# L-D5019-01-05.net
KiCad netlist of a schematic drawn in Altium Designer
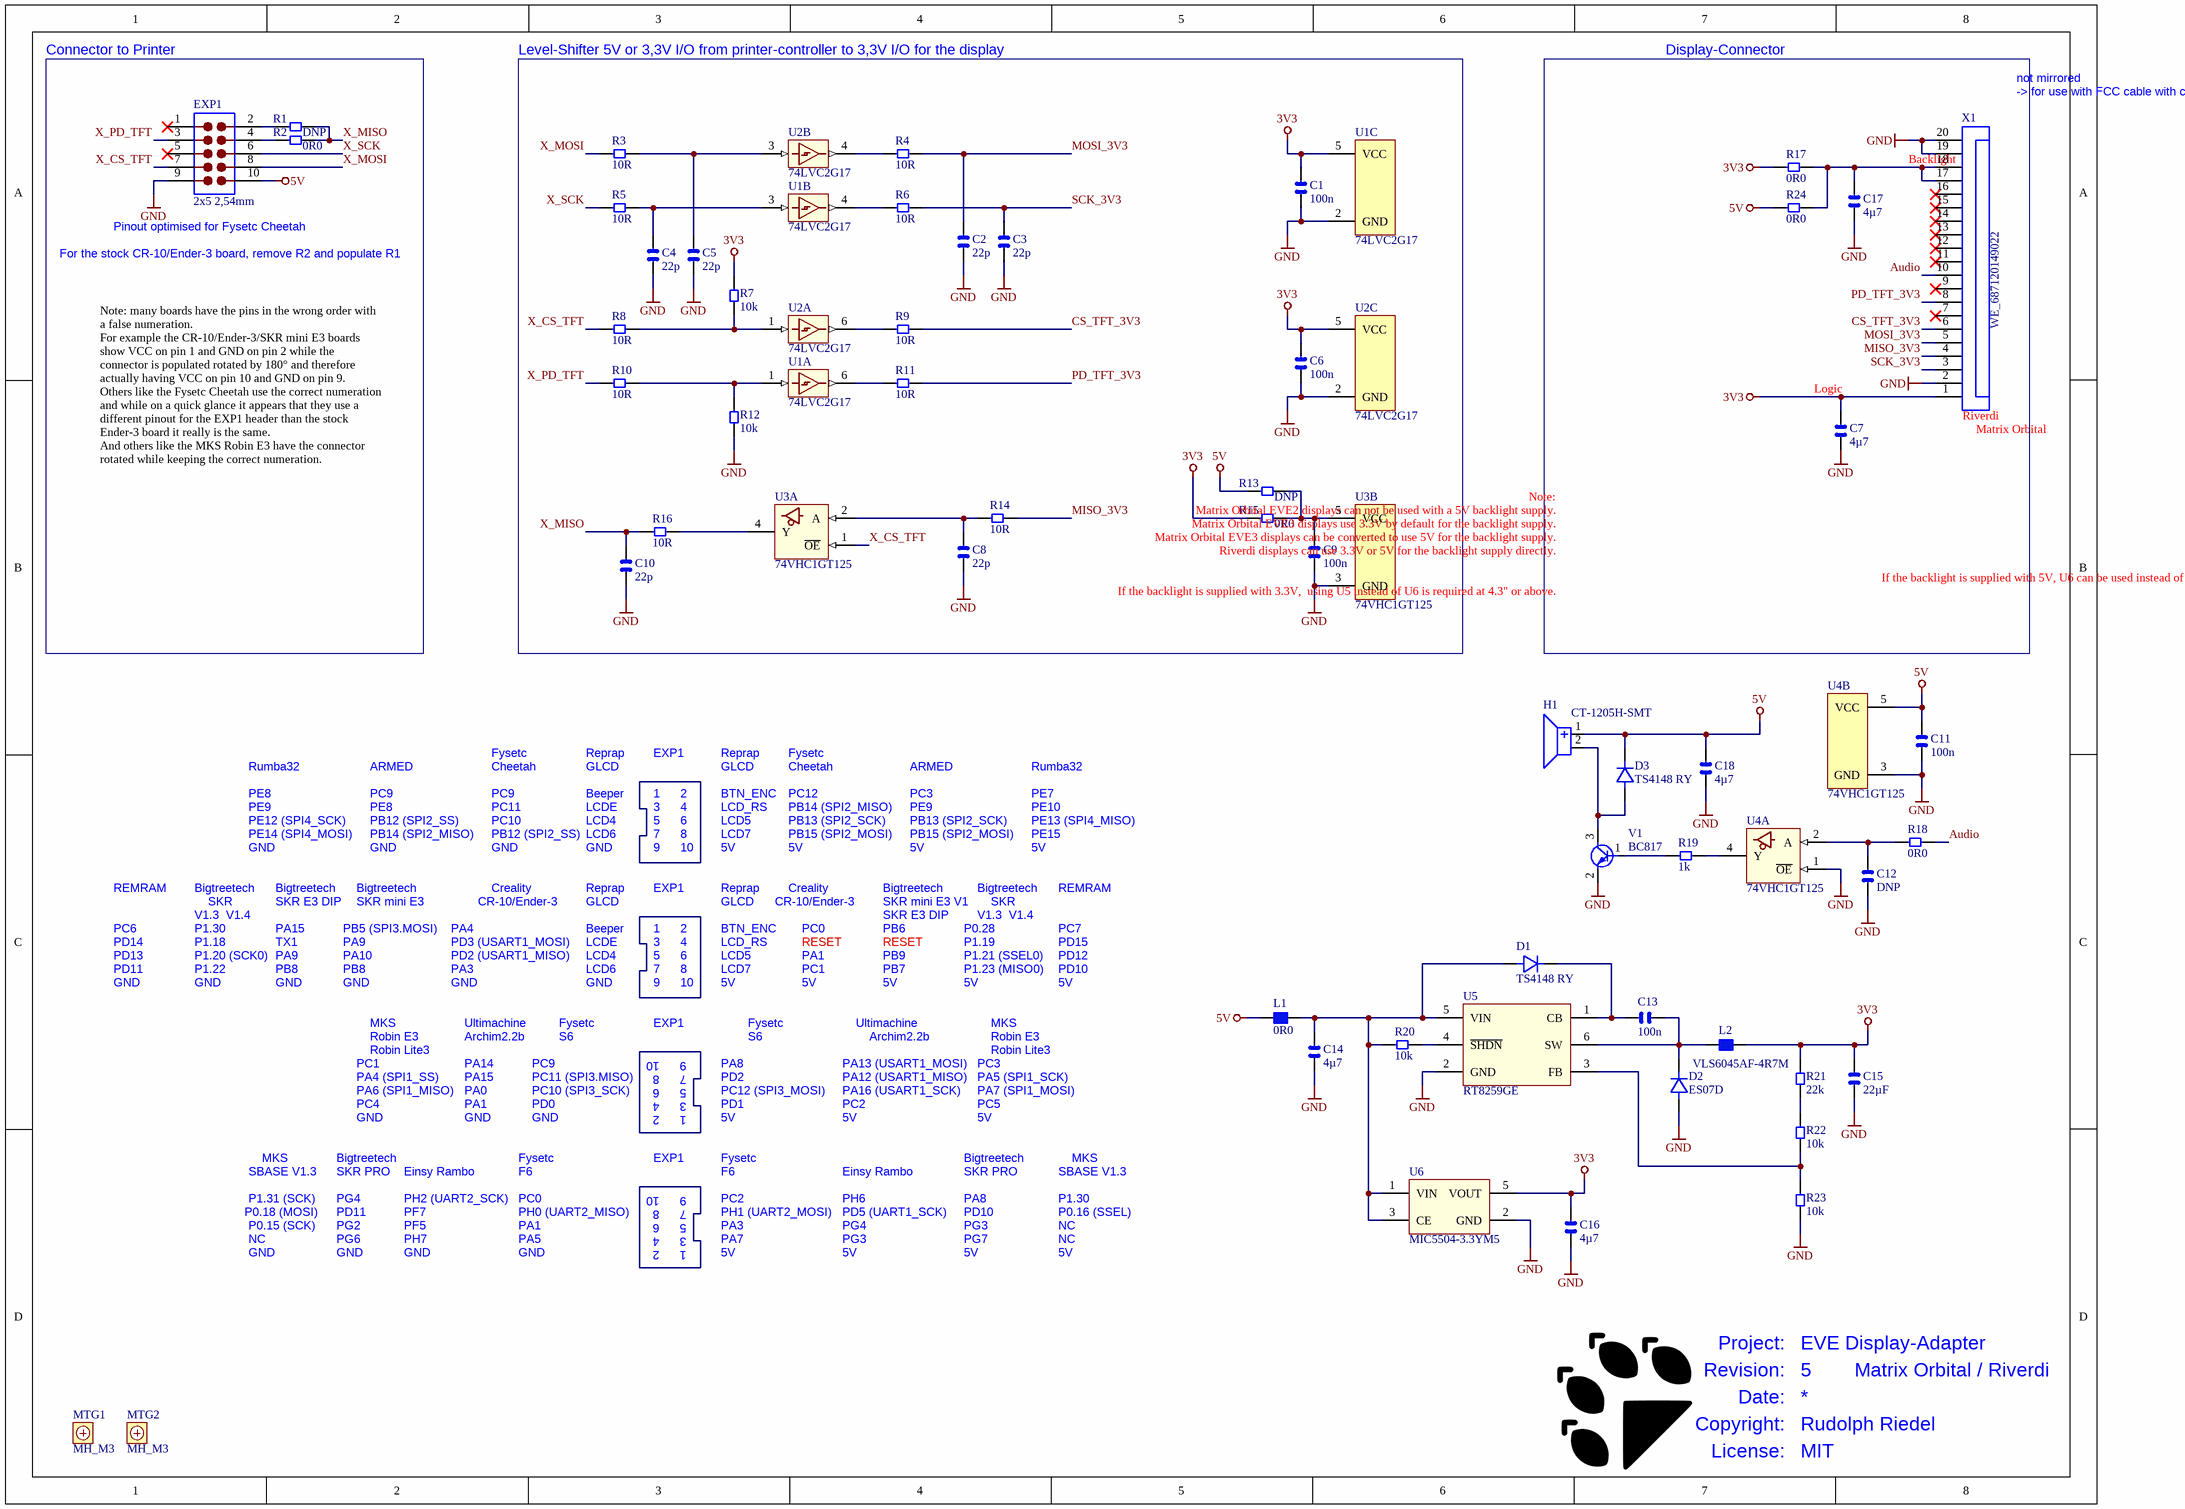
[diagram p0: L-D5019-01-05.SchDoc]

(export (version "E")
  (design (tool "Eeschema 10.0.6"))
  (components
    (comp (ref "C1")
      (value "100n")
      (footprint "CAPC2012X14L")
      (description "0805 Chip Capacitor")
      (fields (field (name "PART NUMBER") "CAPC_0805") (field (name "EDITOR") "rriedel"))
      (libsource (lib "HW-Labor_GF") (part "CAP_2_V2"))
    )
    (comp (ref "C2")
      (value "22p")
      (footprint "CAPC2012X14L")
      (description "0805 Chip Capacitor")
      (fields (field (name "PART NUMBER") "CAPC_0805") (field (name "EDITOR") "rriedel"))
      (libsource (lib "HW-Labor_GF") (part "CAP_2_V2"))
    )
    (comp (ref "C3")
      (value "22p")
      (footprint "CAPC2012X14L")
      (description "0805 Chip Capacitor")
      (fields (field (name "PART NUMBER") "CAPC_0805") (field (name "EDITOR") "rriedel"))
      (libsource (lib "HW-Labor_GF") (part "CAP_2_V2"))
    )
    (comp (ref "C4")
      (value "22p")
      (footprint "CAPC2012X14L")
      (description "0805 Chip Capacitor")
      (fields (field (name "PART NUMBER") "CAPC_0805") (field (name "EDITOR") "rriedel"))
      (libsource (lib "HW-Labor_GF") (part "CAP_2_V2"))
    )
    (comp (ref "C5")
      (value "22p")
      (footprint "CAPC2012X14L")
      (description "0805 Chip Capacitor")
      (fields (field (name "PART NUMBER") "CAPC_0805") (field (name "EDITOR") "rriedel"))
      (libsource (lib "HW-Labor_GF") (part "CAP_2_V2"))
    )
    (comp (ref "C6")
      (value "100n")
      (footprint "CAPC2012X14L")
      (description "0805 Chip Capacitor")
      (fields (field (name "PART NUMBER") "CAPC_0805") (field (name "EDITOR") "rriedel"))
      (libsource (lib "HW-Labor_GF") (part "CAP_2_V2"))
    )
    (comp (ref "C7")
      (value "4µ7")
      (footprint "CAPC2012X14L")
      (description "0805 Chip Capacitor")
      (fields (field (name "PART NUMBER") "CAPC_0805") (field (name "ERSTELLER") "rriedel"))
      (libsource (lib "HW-Labor_GF") (part "CAP_2_V2"))
    )
    (comp (ref "C8")
      (value "22p")
      (footprint "CAPC2012X14L")
      (description "0805 Chip Capacitor")
      (fields (field (name "PART NUMBER") "CAPC_0805") (field (name "EDITOR") "rriedel"))
      (libsource (lib "HW-Labor_GF") (part "CAP_2_V2"))
    )
    (comp (ref "C9")
      (value "100n")
      (footprint "CAPC2012X14L")
      (description "0805 Chip Capacitor")
      (fields (field (name "PART NUMBER") "CAPC_0805") (field (name "EDITOR") "rriedel"))
      (libsource (lib "HW-Labor_GF") (part "CAP_2_V2"))
    )
    (comp (ref "C10")
      (value "22p")
      (footprint "CAPC2012X14L")
      (description "0805 Chip Capacitor")
      (fields (field (name "PART NUMBER") "CAPC_0805") (field (name "EDITOR") "rriedel"))
      (libsource (lib "HW-Labor_GF") (part "CAP_2_V2"))
    )
    (comp (ref "C11")
      (value "100n")
      (footprint "CAPC2012X14L")
      (description "0805 Chip Capacitor")
      (fields (field (name "PART NUMBER") "CAPC_0805") (field (name "EDITOR") "rriedel"))
      (libsource (lib "HW-Labor_GF") (part "CAP_2_V2"))
    )
    (comp (ref "C12")
      (value "DNP")
      (footprint "CAPC2012X14L")
      (description "0805 Chip Capacitor")
      (fields (field (name "PART NUMBER") "CAPC_0805") (field (name "EDITOR") "rriedel"))
      (libsource (lib "HW-Labor_GF") (part "CAP_2_V2"))
    )
    (comp (ref "C13")
      (value "100n")
      (footprint "CAPC2012X14L")
      (description "0805 Chip Capacitor")
      (fields (field (name "PART NUMBER") "CAPC_0805") (field (name "EDITOR") "rriedel"))
      (libsource (lib "HW-Labor_GF") (part "CAP_2_V2"))
    )
    (comp (ref "C14")
      (value "4µ7")
      (footprint "CAPC2012X14L")
      (description "0805 Chip Capacitor")
      (fields (field (name "PART NUMBER") "CAPC_0805") (field (name "ERSTELLER") "rriedel"))
      (libsource (lib "HW-Labor_GF") (part "CAP_2_V2"))
    )
    (comp (ref "C15")
      (value "22µF")
      (footprint "CAPC3216X19N")
      (description "1206 Chip Capacitor")
      (fields (field (name "PART NUMBER") "CAPC_1206") (field (name "EDITOR") "rriedel"))
      (libsource (lib "HW-Labor_GF") (part "CAP_2_V2"))
    )
    (comp (ref "C16")
      (value "4µ7")
      (footprint "CAPC2012X14L")
      (description "0805 Chip Capacitor")
      (fields (field (name "PART NUMBER") "CAPC_0805") (field (name "ERSTELLER") "rriedel"))
      (libsource (lib "HW-Labor_GF") (part "CAP_2_V2"))
    )
    (comp (ref "C17")
      (value "4µ7")
      (footprint "CAPC2012X14L")
      (description "0805 Chip Capacitor")
      (fields (field (name "PART NUMBER") "CAPC_0805") (field (name "ERSTELLER") "rriedel"))
      (libsource (lib "HW-Labor_GF") (part "CAP_2_V2"))
    )
    (comp (ref "C18")
      (value "4µ7")
      (footprint "CAPC2012X14L")
      (description "0805 Chip Capacitor")
      (fields (field (name "PART NUMBER") "CAPC_0805") (field (name "ERSTELLER") "rriedel"))
      (libsource (lib "HW-Labor_GF") (part "CAP_2_V2"))
    )
    (comp (ref "D1")
      (value "TS4148 RY")
      (footprint "DIOC2012X10N")
      (description "Small Signal Diode IF 0.3A, VR 75V, 0805")
      (fields
        (field (name "PART NUMBER") "TSC_TS4148 RY")
        (field (name "MANUFACTURER") "TSC")
        (field (name "EDITOR") "rriedel")
      )
      (libsource (lib "HW-Labor_GF") (part "Diode_A2_K1"))
    )
    (comp (ref "D2")
      (value "ES07D")
      (footprint "DIOM2818X11N")
      (description "Ultrafast Rectifier Surface Mount,  IF 0.5A, VR 100V, DO-219AB, AEC-Q101")
      (fields (field (name "MANUFACTURER") "Vishay") (field (name "EDITOR") "rriedel"))
      (libsource (lib "HW-Labor_GF") (part "Diode_A2_K1"))
    )
    (comp (ref "D3")
      (value "TS4148 RY")
      (footprint "DIOC2012X10N")
      (description "Small Signal Diode IF 0.3A, VR 75V, 0805")
      (fields
        (field (name "PART NUMBER") "TSC_TS4148 RY")
        (field (name "MANUFACTURER") "TSC")
        (field (name "EDITOR") "rriedel")
      )
      (libsource (lib "HW-Labor_GF") (part "Diode_A2_K1"))
    )
    (comp (ref "EXP1")
      (value "2x5 2,54mm")
      (footprint "PINH_2x5_2_54mm_shroud")
      (description "Pin-Header 2,54 mm 2x5pins, shrouded")
      (fields (field (name "PART NUMBER") "PINH_2x5_2_54") (field (name "EDITOR") "rriedel"))
      (libsource (lib "HW-Labor_GF") (part "CONM_2x5_V2"))
    )
    (comp (ref "H1")
      (value "CT-1205H-SMT")
      (footprint "CT-1205H-SMT")
      (description "Speaker, Magnetic, 47R, 60mA, 88dBA, SMT, 12.8 x 12.8 mm,  height 10 mm")
      (fields
        (field (name "MANUFACTURER") "CUI")
        (field (name "DISTRIBUTOR_1_PART_NUMBER") "102-1266-1-ND")
        (field (name "EDITOR") "rriedel")
      )
      (libsource (lib "HW-Labor_GF") (part "Speaker"))
    )
    (comp (ref "L1")
      (value "0R0")
      (footprint "INDC2012X10L")
      (description "0805 Chip Inductor")
      (fields (field (name "PART NUMBER") "INDC_0805") (field (name "EDITOR") "rriedel"))
      (libsource (lib "HW-Labor_GF") (part "IND_2_V1"))
    )
    (comp (ref "L2")
      (value "VLS6045AF-4R7M")
      (footprint "PowerInductor_6x6")
      (description "4,7µH, shielded, 4,7A, 26mR")
      (fields
        (field (name "MANUFACTURER") "TDK")
        (field (name "DISTRIBUTOR_1_PART_NUMBER") "445-180835-1-ND")
        (field (name "EDITOR") "rriedel")
      )
      (libsource (lib "HW-Labor_GF") (part "IND_2_V1"))
    )
    (comp (ref "MTG1")
      (value "MH_M3")
      (footprint "HOLE_3_2MM")
      (description "Mounting-Hole for M3 screws")
      (fields (field (name "EDITOR") "rriedel"))
      (libsource (lib "HW-Labor_GF") (part "MTG_V1"))
    )
    (comp (ref "MTG2")
      (value "MH_M3")
      (footprint "HOLE_3_2MM")
      (description "Mounting-Hole for M3 screws")
      (fields (field (name "EDITOR") "rriedel"))
      (libsource (lib "HW-Labor_GF") (part "MTG_V1"))
    )
    (comp (ref "R1")
      (value "DNP")
      (footprint "RESC2012X06L")
      (description "0805 Chip Resistor")
      (fields (field (name "PART NUMBER") "RESC_0805") (field (name "EDITOR") "rriedel"))
      (libsource (lib "HW-Labor_GF") (part "RES_2_V2"))
    )
    (comp (ref "R2")
      (value "0R0")
      (footprint "RESC2012X06L")
      (description "0805 Chip Resistor")
      (fields (field (name "PART NUMBER") "RESC_0805") (field (name "EDITOR") "rriedel"))
      (libsource (lib "HW-Labor_GF") (part "RES_2_V2"))
    )
    (comp (ref "R3")
      (value "10R")
      (footprint "RESC2012X06L")
      (description "0805 Chip Resistor")
      (fields (field (name "PART NUMBER") "RESC_0805") (field (name "EDITOR") "rriedel"))
      (libsource (lib "HW-Labor_GF") (part "RES_2_V2"))
    )
    (comp (ref "R4")
      (value "10R")
      (footprint "RESC2012X06L")
      (description "0805 Chip Resistor")
      (fields (field (name "PART NUMBER") "RESC_0805") (field (name "EDITOR") "rriedel"))
      (libsource (lib "HW-Labor_GF") (part "RES_2_V2"))
    )
    (comp (ref "R5")
      (value "10R")
      (footprint "RESC2012X06L")
      (description "0805 Chip Resistor")
      (fields (field (name "PART NUMBER") "RESC_0805") (field (name "EDITOR") "rriedel"))
      (libsource (lib "HW-Labor_GF") (part "RES_2_V2"))
    )
    (comp (ref "R6")
      (value "10R")
      (footprint "RESC2012X06L")
      (description "0805 Chip Resistor")
      (fields (field (name "PART NUMBER") "RESC_0805") (field (name "EDITOR") "rriedel"))
      (libsource (lib "HW-Labor_GF") (part "RES_2_V2"))
    )
    (comp (ref "R7")
      (value "10k")
      (footprint "RESC2012X06L")
      (description "0805 Chip Resistor")
      (fields (field (name "PART NUMBER") "RESC_0805") (field (name "EDITOR") "rriedel"))
      (libsource (lib "HW-Labor_GF") (part "RES_2_V2"))
    )
    (comp (ref "R8")
      (value "10R")
      (footprint "RESC2012X06L")
      (description "0805 Chip Resistor")
      (fields (field (name "PART NUMBER") "RESC_0805") (field (name "EDITOR") "rriedel"))
      (libsource (lib "HW-Labor_GF") (part "RES_2_V2"))
    )
    (comp (ref "R9")
      (value "10R")
      (footprint "RESC2012X06L")
      (description "0805 Chip Resistor")
      (fields (field (name "PART NUMBER") "RESC_0805") (field (name "EDITOR") "rriedel"))
      (libsource (lib "HW-Labor_GF") (part "RES_2_V2"))
    )
    (comp (ref "R10")
      (value "10R")
      (footprint "RESC2012X06L")
      (description "0805 Chip Resistor")
      (fields (field (name "PART NUMBER") "RESC_0805") (field (name "EDITOR") "rriedel"))
      (libsource (lib "HW-Labor_GF") (part "RES_2_V2"))
    )
    (comp (ref "R11")
      (value "10R")
      (footprint "RESC2012X06L")
      (description "0805 Chip Resistor")
      (fields (field (name "PART NUMBER") "RESC_0805") (field (name "EDITOR") "rriedel"))
      (libsource (lib "HW-Labor_GF") (part "RES_2_V2"))
    )
    (comp (ref "R12")
      (value "10k")
      (footprint "RESC2012X06L")
      (description "0805 Chip Resistor")
      (fields (field (name "PART NUMBER") "RESC_0805") (field (name "EDITOR") "rriedel"))
      (libsource (lib "HW-Labor_GF") (part "RES_2_V2"))
    )
    (comp (ref "R13")
      (value "DNP")
      (footprint "RESC2012X06L")
      (description "0805 Chip Resistor")
      (fields (field (name "PART NUMBER") "RESC_0805") (field (name "EDITOR") "rriedel"))
      (libsource (lib "HW-Labor_GF") (part "RES_2_V2"))
    )
    (comp (ref "R14")
      (value "10R")
      (footprint "RESC2012X06L")
      (description "0805 Chip Resistor")
      (fields (field (name "PART NUMBER") "RESC_0805") (field (name "EDITOR") "rriedel"))
      (libsource (lib "HW-Labor_GF") (part "RES_2_V2"))
    )
    (comp (ref "R15")
      (value "0R0")
      (footprint "RESC2012X06L")
      (description "0805 Chip Resistor")
      (fields (field (name "PART NUMBER") "RESC_0805") (field (name "EDITOR") "rriedel"))
      (libsource (lib "HW-Labor_GF") (part "RES_2_V2"))
    )
    (comp (ref "R16")
      (value "10R")
      (footprint "RESC2012X06L")
      (description "0805 Chip Resistor")
      (fields (field (name "PART NUMBER") "RESC_0805") (field (name "EDITOR") "rriedel"))
      (libsource (lib "HW-Labor_GF") (part "RES_2_V2"))
    )
    (comp (ref "R17")
      (value "0R0")
      (footprint "RESC2012X06L")
      (description "0805 Chip Resistor")
      (fields (field (name "PART NUMBER") "RESC_0805") (field (name "EDITOR") "rriedel"))
      (libsource (lib "HW-Labor_GF") (part "RES_2_V2"))
    )
    (comp (ref "R18")
      (value "0R0")
      (footprint "RESC2012X06L")
      (description "0805 Chip Resistor")
      (fields (field (name "PART NUMBER") "RESC_0805") (field (name "EDITOR") "rriedel"))
      (libsource (lib "HW-Labor_GF") (part "RES_2_V2"))
    )
    (comp (ref "R19")
      (value "1k")
      (footprint "RESC2012X06L")
      (description "0805 Chip Resistor")
      (fields (field (name "PART NUMBER") "RESC_0805") (field (name "EDITOR") "rriedel"))
      (libsource (lib "HW-Labor_GF") (part "RES_2_V2"))
    )
    (comp (ref "R20")
      (value "10k")
      (footprint "RESC2012X06L")
      (description "0805 Chip Resistor")
      (fields (field (name "PART NUMBER") "RESC_0805") (field (name "EDITOR") "rriedel"))
      (libsource (lib "HW-Labor_GF") (part "RES_2_V2"))
    )
    (comp (ref "R21")
      (value "22k")
      (footprint "RESC2012X06L")
      (description "0805 Chip Resistor")
      (fields (field (name "PART NUMBER") "RESC_0805") (field (name "EDITOR") "rriedel"))
      (libsource (lib "HW-Labor_GF") (part "RES_2_V2"))
    )
    (comp (ref "R22")
      (value "10k")
      (footprint "RESC2012X06L")
      (description "0805 Chip Resistor")
      (fields (field (name "PART NUMBER") "RESC_0805") (field (name "EDITOR") "rriedel"))
      (libsource (lib "HW-Labor_GF") (part "RES_2_V2"))
    )
    (comp (ref "R23")
      (value "10k")
      (footprint "RESC2012X06L")
      (description "0805 Chip Resistor")
      (fields (field (name "PART NUMBER") "RESC_0805") (field (name "EDITOR") "rriedel"))
      (libsource (lib "HW-Labor_GF") (part "RES_2_V2"))
    )
    (comp (ref "R24")
      (value "0R0")
      (footprint "RESC2012X06L")
      (description "0805 Chip Resistor")
      (fields (field (name "PART NUMBER") "RESC_0805") (field (name "EDITOR") "rriedel"))
      (libsource (lib "HW-Labor_GF") (part "RES_2_V2"))
    )
    (comp (ref "U1")
      (value "74LVC2G17")
      (footprint "SOT95P280X110-6N")
      (description "Dual Schmitt-Trigger Buffer with 5.5V tolerant inputs")
      (fields
        (field (name "MANUFACTURER") "TI")
        (field (name "DISTRIBUTOR_1_PART_NUMBER") "296-SN74LVC2G17DBVRCT-ND‎")
        (field (name "EDITOR") "rriedel")
      )
      (libsource (lib "HW-Labor_GF") (part "74LVC2G17"))
    )
    (comp (ref "U2")
      (value "74LVC2G17")
      (footprint "SOT95P280X110-6N")
      (description "Dual Schmitt-Trigger Buffer with 5.5V tolerant inputs")
      (fields
        (field (name "MANUFACTURER") "TI")
        (field (name "DISTRIBUTOR_1_PART_NUMBER") "296-SN74LVC2G17DBVRCT-ND‎")
        (field (name "EDITOR") "rriedel")
      )
      (libsource (lib "HW-Labor_GF") (part "74LVC2G17"))
    )
    (comp (ref "U3")
      (value "74VHC1GT125")
      (footprint "SOT95P280X110-5N")
      (description "1x Buffer with OE; 3-state,Level Shifter 3,3V to 5V and 5V to 3.3V")
      (fields
        (field (name "MANUFACTURER") "ON Semiconductor")
        (field (name "DISTRIBUTOR_1_PART_NUMBER") "1703291")
        (field (name "EDITOR") "rriedel")
      )
      (libsource (lib "HW-Labor_GF") (part "74LVC1G125G"))
    )
    (comp (ref "U4")
      (value "74VHC1GT125")
      (footprint "SOT95P280X110-5N")
      (description "1x Buffer with OE; 3-state,Level Shifter 3,3V to 5V and 5V to 3.3V")
      (fields
        (field (name "MANUFACTURER") "ON Semiconductor")
        (field (name "DISTRIBUTOR_1_PART_NUMBER") "1703291")
        (field (name "EDITOR") "rriedel")
      )
      (libsource (lib "") (part "74LVC1G125G_1"))
    )
    (comp (ref "U5")
      (value "RT8259GE")
      (footprint "SOT95P280X110-6N")
      (description "Step-Down DC/DC Regulator, 24V, 1.2A, 1,4MHz")
      (fields
        (field (name "MANUFACTURER") "Richtek")
        (field (name "DISTRIBUTOR_1_PART_NUMBER") "1028-1497-1-ND")
        (field (name "EDITOR") "rriedel")
      )
      (libsource (lib "HW-Labor_GF") (part "StepDown_SOT23-6"))
    )
    (comp (ref "U6")
      (value "MIC5504-3.3YM5")
      (footprint "SOT95P280X110-5N")
      (description "300 mA LDO,  Vin=2,5V…5,5V, Vout= 3,3V, -40°C..125°C")
      (fields
        (field (name "MANUFACTURER") "Microchip")
        (field (name "DISTRIBUTOR_1_PART_NUMBER") "2510377")
        (field (name "EDITOR") "rriedel")
      )
      (libsource (lib "HW-Labor_GF") (part "LDO_SOT23-5"))
    )
    (comp (ref "V1")
      (value "BC817")
      (footprint "SOT95P280X110-3N")
      (description "NPN Transistor SOT23, 1=B, 2=C, 3=E")
      (fields (field (name "EDITOR") "rriedel"))
      (libsource (lib "HW-Labor_GF") (part "NPN_B1_C2_E3"))
    )
    (comp (ref "X1")
      (value "WE_687120149022")
      (footprint "WE_687120149022")
      (description "20pin WR-FPC 0.50 mm SMT ZIF Horizontal - Bottom Contact")
      (fields
        (field (name "MANUFACTURER") "Wuerth")
        (field (name "DISTRIBUTOR_1_PART_NUMBER") "732-6002-1-ND")
        (field (name "EDITOR") "rriedel")
      )
      (libsource (lib "HW-Labor_GF") (part "FPC_20"))
    )
  )
  (nets
    (net (code "1") (name "/Audio") (class "Default")
      (node (ref "R18") (pin "2") (pinfunction "2_2") (pintype "passive"))
      (node (ref "X1") (pin "10") (pinfunction "10_10") (pintype "passive"))
    )
    (net (code "2") (name "/CS_TFT_3V3") (class "Default")
      (node (ref "R9") (pin "2") (pinfunction "2_2") (pintype "passive"))
      (node (ref "X1") (pin "6") (pinfunction "6_6") (pintype "passive"))
    )
    (net (code "3") (name "/MISO_3V3") (class "Default")
      (node (ref "R14") (pin "2") (pinfunction "2_2") (pintype "passive"))
      (node (ref "X1") (pin "4") (pinfunction "4_4") (pintype "passive"))
    )
    (net (code "4") (name "/MOSI_3V3") (class "Default")
      (node (ref "C2") (pin "2") (pinfunction "2_2") (pintype "passive"))
      (node (ref "R4") (pin "2") (pinfunction "2_2") (pintype "passive"))
      (node (ref "X1") (pin "5") (pinfunction "5_5") (pintype "passive"))
    )
    (net (code "5") (name "/PD_TFT_3V3") (class "Default")
      (node (ref "R11") (pin "2") (pinfunction "2_2") (pintype "passive"))
      (node (ref "X1") (pin "8") (pinfunction "8_8") (pintype "passive"))
    )
    (net (code "6") (name "/SCK_3V3") (class "Default")
      (node (ref "C3") (pin "2") (pinfunction "2_2") (pintype "passive"))
      (node (ref "R6") (pin "2") (pinfunction "2_2") (pintype "passive"))
      (node (ref "X1") (pin "3") (pinfunction "3_3") (pintype "passive"))
    )
    (net (code "7") (name "/X_CS_TFT") (class "Default")
      (node (ref "EXP1") (pin "7") (pinfunction "7_7") (pintype "passive"))
      (node (ref "R8") (pin "1") (pinfunction "1_1") (pintype "passive"))
      (node (ref "U3") (pin "1") (pinfunction "~{OE}_1") (pintype "input"))
    )
    (net (code "8") (name "/X_MISO") (class "Default")
      (node (ref "C10") (pin "2") (pinfunction "2_2") (pintype "passive"))
      (node (ref "R1") (pin "2") (pinfunction "2_2") (pintype "passive"))
      (node (ref "R16") (pin "1") (pinfunction "1_1") (pintype "passive"))
      (node (ref "R2") (pin "2") (pinfunction "2_2") (pintype "passive"))
    )
    (net (code "9") (name "/X_MOSI") (class "Default")
      (node (ref "EXP1") (pin "8") (pinfunction "8_8") (pintype "passive"))
      (node (ref "R3") (pin "1") (pinfunction "1_1") (pintype "passive"))
    )
    (net (code "10") (name "/X_PD_TFT") (class "Default")
      (node (ref "EXP1") (pin "3") (pinfunction "3_3") (pintype "passive"))
      (node (ref "R10") (pin "1") (pinfunction "1_1") (pintype "passive"))
    )
    (net (code "11") (name "/X_SCK") (class "Default")
      (node (ref "EXP1") (pin "6") (pinfunction "6_6") (pintype "passive"))
      (node (ref "R5") (pin "1") (pinfunction "1_1") (pintype "passive"))
    )
    (net (code "12") (name "3V3") (class "Default")
      (node (ref "C1") (pin "2") (pinfunction "2_2") (pintype "passive"))
      (node (ref "C15") (pin "2") (pinfunction "2_2") (pintype "passive"))
      (node (ref "C16") (pin "2") (pinfunction "2_2") (pintype "passive"))
      (node (ref "C6") (pin "2") (pinfunction "2_2") (pintype "passive"))
      (node (ref "C7") (pin "2") (pinfunction "2_2") (pintype "passive"))
      (node (ref "L2") (pin "2") (pinfunction "2_2") (pintype "passive"))
      (node (ref "R15") (pin "1") (pinfunction "1_1") (pintype "passive"))
      (node (ref "R17") (pin "1") (pinfunction "1_1") (pintype "passive"))
      (node (ref "R21") (pin "2") (pinfunction "2_2") (pintype "passive"))
      (node (ref "R7") (pin "2") (pinfunction "2_2") (pintype "passive"))
      (node (ref "U1") (pin "5") (pinfunction "VCC_5") (pintype "power_in"))
      (node (ref "U2") (pin "5") (pinfunction "VCC_5") (pintype "power_in"))
      (node (ref "U6") (pin "5") (pinfunction "VOUT_5") (pintype "passive"))
      (node (ref "X1") (pin "1") (pinfunction "1_1") (pintype "passive"))
    )
    (net (code "13") (name "5V") (class "Default")
      (node (ref "C11") (pin "2") (pinfunction "2_2") (pintype "passive"))
      (node (ref "C18") (pin "2") (pinfunction "2_2") (pintype "passive"))
      (node (ref "D3") (pin "1") (pinfunction "1_1") (pintype "passive"))
      (node (ref "EXP1") (pin "10") (pinfunction "10_10") (pintype "passive"))
      (node (ref "H1") (pin "1") (pinfunction "1_1") (pintype "passive"))
      (node (ref "L1") (pin "1") (pinfunction "1_1") (pintype "passive"))
      (node (ref "R13") (pin "1") (pinfunction "1_1") (pintype "passive"))
      (node (ref "R24") (pin "1") (pinfunction "1_1") (pintype "passive"))
      (node (ref "U4") (pin "5") (pinfunction "VCC_5") (pintype "passive"))
    )
    (net (code "14") (name "GND") (class "Default")
      (node (ref "C1") (pin "1") (pinfunction "1_1") (pintype "passive"))
      (node (ref "C10") (pin "1") (pinfunction "1_1") (pintype "passive"))
      (node (ref "C11") (pin "1") (pinfunction "1_1") (pintype "passive"))
      (node (ref "C12") (pin "1") (pinfunction "1_1") (pintype "passive"))
      (node (ref "C14") (pin "1") (pinfunction "1_1") (pintype "passive"))
      (node (ref "C15") (pin "1") (pinfunction "1_1") (pintype "passive"))
      (node (ref "C16") (pin "1") (pinfunction "1_1") (pintype "passive"))
      (node (ref "C17") (pin "1") (pinfunction "1_1") (pintype "passive"))
      (node (ref "C18") (pin "1") (pinfunction "1_1") (pintype "passive"))
      (node (ref "C2") (pin "1") (pinfunction "1_1") (pintype "passive"))
      (node (ref "C3") (pin "1") (pinfunction "1_1") (pintype "passive"))
      (node (ref "C4") (pin "1") (pinfunction "1_1") (pintype "passive"))
      (node (ref "C5") (pin "1") (pinfunction "1_1") (pintype "passive"))
      (node (ref "C6") (pin "1") (pinfunction "1_1") (pintype "passive"))
      (node (ref "C7") (pin "1") (pinfunction "1_1") (pintype "passive"))
      (node (ref "C8") (pin "1") (pinfunction "1_1") (pintype "passive"))
      (node (ref "C9") (pin "1") (pinfunction "1_1") (pintype "passive"))
      (node (ref "D2") (pin "2") (pinfunction "2_2") (pintype "passive"))
      (node (ref "EXP1") (pin "9") (pinfunction "9_9") (pintype "passive"))
      (node (ref "R12") (pin "1") (pinfunction "1_1") (pintype "passive"))
      (node (ref "R23") (pin "1") (pinfunction "1_1") (pintype "passive"))
      (node (ref "U1") (pin "2") (pinfunction "GND_2") (pintype "power_in"))
      (node (ref "U2") (pin "2") (pinfunction "GND_2") (pintype "power_in"))
      (node (ref "U3") (pin "3") (pinfunction "GND_3") (pintype "passive"))
      (node (ref "U4") (pin "1") (pinfunction "~{OE}_1") (pintype "input"))
      (node (ref "U4") (pin "3") (pinfunction "GND_3") (pintype "passive"))
      (node (ref "U5") (pin "2") (pinfunction "GND_2") (pintype "power_in"))
      (node (ref "U6") (pin "2") (pinfunction "GND_2") (pintype "passive"))
      (node (ref "V1") (pin "2") (pinfunction "2_2") (pintype "passive"))
      (node (ref "X1") (pin "19") (pinfunction "19_19") (pintype "passive"))
      (node (ref "X1") (pin "2") (pinfunction "2_2") (pintype "passive"))
      (node (ref "X1") (pin "20") (pinfunction "20_20") (pintype "passive"))
    )
    (net (code "15") (name "Net-(C17-Pad2)") (class "Default")
      (node (ref "C17") (pin "2") (pinfunction "2_2") (pintype "passive"))
      (node (ref "R17") (pin "2") (pinfunction "2_2") (pintype "passive"))
      (node (ref "R24") (pin "2") (pinfunction "2_2") (pintype "passive"))
      (node (ref "X1") (pin "17") (pinfunction "17_17") (pintype "passive"))
      (node (ref "X1") (pin "18") (pinfunction "18_18") (pintype "passive"))
    )
    (net (code "16") (name "Net-(D3-Pad2)") (class "Default")
      (node (ref "D3") (pin "2") (pinfunction "2_2") (pintype "passive"))
      (node (ref "H1") (pin "2") (pinfunction "2_2") (pintype "passive"))
      (node (ref "V1") (pin "3") (pinfunction "3_3") (pintype "passive"))
    )
    (net (code "17") (name "Net-(EXP1-Pad2)") (class "Default")
      (node (ref "EXP1") (pin "2") (pinfunction "2_2") (pintype "passive"))
      (node (ref "R1") (pin "1") (pinfunction "1_1") (pintype "passive"))
    )
    (net (code "18") (name "Net-(EXP1-Pad4)") (class "Default")
      (node (ref "EXP1") (pin "4") (pinfunction "4_4") (pintype "passive"))
      (node (ref "R2") (pin "1") (pinfunction "1_1") (pintype "passive"))
    )
    (net (code "19") (name "Net-(R19-Pad2)") (class "Default")
      (node (ref "R19") (pin "2") (pinfunction "2_2") (pintype "passive"))
      (node (ref "V1") (pin "1") (pinfunction "1_1") (pintype "passive"))
    )
    (net (code "20") (name "Net-(R21-Pad1)") (class "Default")
      (node (ref "R21") (pin "1") (pinfunction "1_1") (pintype "passive"))
      (node (ref "R22") (pin "2") (pinfunction "2_2") (pintype "passive"))
    )
    (net (code "21") (name "Net-(U1A-1A)") (class "Default")
      (node (ref "R10") (pin "2") (pinfunction "2_2") (pintype "passive"))
      (node (ref "R12") (pin "2") (pinfunction "2_2") (pintype "passive"))
      (node (ref "U1") (pin "1") (pinfunction "1A_1") (pintype "input"))
    )
    (net (code "22") (name "Net-(U1A-1Y)") (class "Default")
      (node (ref "R11") (pin "1") (pinfunction "1_1") (pintype "passive"))
      (node (ref "U1") (pin "6") (pinfunction "1Y_6") (pintype "output"))
    )
    (net (code "23") (name "Net-(U1B-2A)") (class "Default")
      (node (ref "C4") (pin "2") (pinfunction "2_2") (pintype "passive"))
      (node (ref "R5") (pin "2") (pinfunction "2_2") (pintype "passive"))
      (node (ref "U1") (pin "3") (pinfunction "2A_3") (pintype "input"))
    )
    (net (code "24") (name "Net-(U1B-2Y)") (class "Default")
      (node (ref "R6") (pin "1") (pinfunction "1_1") (pintype "passive"))
      (node (ref "U1") (pin "4") (pinfunction "2Y_4") (pintype "output"))
    )
    (net (code "25") (name "Net-(U2A-1A)") (class "Default")
      (node (ref "R7") (pin "1") (pinfunction "1_1") (pintype "passive"))
      (node (ref "R8") (pin "2") (pinfunction "2_2") (pintype "passive"))
      (node (ref "U2") (pin "1") (pinfunction "1A_1") (pintype "input"))
    )
    (net (code "26") (name "Net-(U2A-1Y)") (class "Default")
      (node (ref "R9") (pin "1") (pinfunction "1_1") (pintype "passive"))
      (node (ref "U2") (pin "6") (pinfunction "1Y_6") (pintype "output"))
    )
    (net (code "27") (name "Net-(U2B-2A)") (class "Default")
      (node (ref "C5") (pin "2") (pinfunction "2_2") (pintype "passive"))
      (node (ref "R3") (pin "2") (pinfunction "2_2") (pintype "passive"))
      (node (ref "U2") (pin "3") (pinfunction "2A_3") (pintype "input"))
    )
    (net (code "28") (name "Net-(U2B-2Y)") (class "Default")
      (node (ref "R4") (pin "1") (pinfunction "1_1") (pintype "passive"))
      (node (ref "U2") (pin "4") (pinfunction "2Y_4") (pintype "output"))
    )
    (net (code "29") (name "Net-(U3A-A)") (class "Default")
      (node (ref "C8") (pin "2") (pinfunction "2_2") (pintype "passive"))
      (node (ref "R14") (pin "1") (pinfunction "1_1") (pintype "passive"))
      (node (ref "U3") (pin "2") (pinfunction "A_2") (pintype "input"))
    )
    (net (code "30") (name "Net-(U3A-Y)") (class "Default")
      (node (ref "R16") (pin "2") (pinfunction "2_2") (pintype "passive"))
      (node (ref "U3") (pin "4") (pinfunction "Y_4") (pintype "tri_state"))
    )
    (net (code "31") (name "Net-(U3B-VCC)") (class "Default")
      (node (ref "C9") (pin "2") (pinfunction "2_2") (pintype "passive"))
      (node (ref "R13") (pin "2") (pinfunction "2_2") (pintype "passive"))
      (node (ref "R15") (pin "2") (pinfunction "2_2") (pintype "passive"))
      (node (ref "U3") (pin "5") (pinfunction "VCC_5") (pintype "passive"))
    )
    (net (code "32") (name "Net-(U4A-A)") (class "Default")
      (node (ref "C12") (pin "2") (pinfunction "2_2") (pintype "passive"))
      (node (ref "R18") (pin "1") (pinfunction "1_1") (pintype "passive"))
      (node (ref "U4") (pin "2") (pinfunction "A_2") (pintype "input"))
    )
    (net (code "33") (name "Net-(U4A-Y)") (class "Default")
      (node (ref "R19") (pin "1") (pinfunction "1_1") (pintype "passive"))
      (node (ref "U4") (pin "4") (pinfunction "Y_4") (pintype "tri_state"))
    )
    (net (code "34") (name "Net-(U5-CB)") (class "Default")
      (node (ref "C13") (pin "1") (pinfunction "1_1") (pintype "passive"))
      (node (ref "D1") (pin "1") (pinfunction "1_1") (pintype "passive"))
      (node (ref "U5") (pin "1") (pinfunction "CB_1") (pintype "passive"))
    )
    (net (code "35") (name "Net-(U5-FB)") (class "Default")
      (node (ref "R22") (pin "1") (pinfunction "1_1") (pintype "passive"))
      (node (ref "R23") (pin "2") (pinfunction "2_2") (pintype "passive"))
      (node (ref "U5") (pin "3") (pinfunction "FB_3") (pintype "passive"))
    )
    (net (code "36") (name "Net-(U5-SW)") (class "Default")
      (node (ref "C13") (pin "2") (pinfunction "2_2") (pintype "passive"))
      (node (ref "D2") (pin "1") (pinfunction "1_1") (pintype "passive"))
      (node (ref "L2") (pin "1") (pinfunction "1_1") (pintype "passive"))
      (node (ref "U5") (pin "6") (pinfunction "SW_6") (pintype "passive"))
    )
    (net (code "37") (name "Net-(U5-VIN)") (class "Default")
      (node (ref "C14") (pin "2") (pinfunction "2_2") (pintype "passive"))
      (node (ref "D1") (pin "2") (pinfunction "2_2") (pintype "passive"))
      (node (ref "L1") (pin "2") (pinfunction "2_2") (pintype "passive"))
      (node (ref "R20") (pin "1") (pinfunction "1_1") (pintype "passive"))
      (node (ref "U5") (pin "5") (pinfunction "VIN_5") (pintype "power_in"))
      (node (ref "U6") (pin "1") (pinfunction "VIN_1") (pintype "passive"))
      (node (ref "U6") (pin "3") (pinfunction "CE_3") (pintype "passive"))
    )
    (net (code "38") (name "Net-(U5-~{SHDN})") (class "Default")
      (node (ref "R20") (pin "2") (pinfunction "2_2") (pintype "passive"))
      (node (ref "U5") (pin "4") (pinfunction "~{SHDN}_4") (pintype "passive"))
    )
    (net (code "39") (name "unconnected-(EXP1-Pad1)") (class "Default")
      (node (ref "EXP1") (pin "1") (pinfunction "1_1") (pintype "passive+no_connect"))
    )
    (net (code "40") (name "unconnected-(EXP1-Pad5)") (class "Default")
      (node (ref "EXP1") (pin "5") (pinfunction "5_5") (pintype "passive+no_connect"))
    )
    (net (code "41") (name "unconnected-(X1-Pad7)") (class "Default")
      (node (ref "X1") (pin "7") (pinfunction "7_7") (pintype "passive+no_connect"))
    )
    (net (code "42") (name "unconnected-(X1-Pad9)") (class "Default")
      (node (ref "X1") (pin "9") (pinfunction "9_9") (pintype "passive+no_connect"))
    )
    (net (code "43") (name "unconnected-(X1-Pad11)") (class "Default")
      (node (ref "X1") (pin "11") (pinfunction "11_11") (pintype "passive+no_connect"))
    )
    (net (code "44") (name "unconnected-(X1-Pad12)") (class "Default")
      (node (ref "X1") (pin "12") (pinfunction "12_12") (pintype "passive+no_connect"))
    )
    (net (code "45") (name "unconnected-(X1-Pad13)") (class "Default")
      (node (ref "X1") (pin "13") (pinfunction "13_13") (pintype "passive+no_connect"))
    )
    (net (code "46") (name "unconnected-(X1-Pad14)") (class "Default")
      (node (ref "X1") (pin "14") (pinfunction "14_14") (pintype "passive+no_connect"))
    )
    (net (code "47") (name "unconnected-(X1-Pad15)") (class "Default")
      (node (ref "X1") (pin "15") (pinfunction "15_15") (pintype "passive+no_connect"))
    )
    (net (code "48") (name "unconnected-(X1-Pad16)") (class "Default")
      (node (ref "X1") (pin "16") (pinfunction "16_16") (pintype "passive+no_connect"))
    )
  )
)
